# BreakoutV2.net
KiCad netlist of a schematic drawn in EAGLE
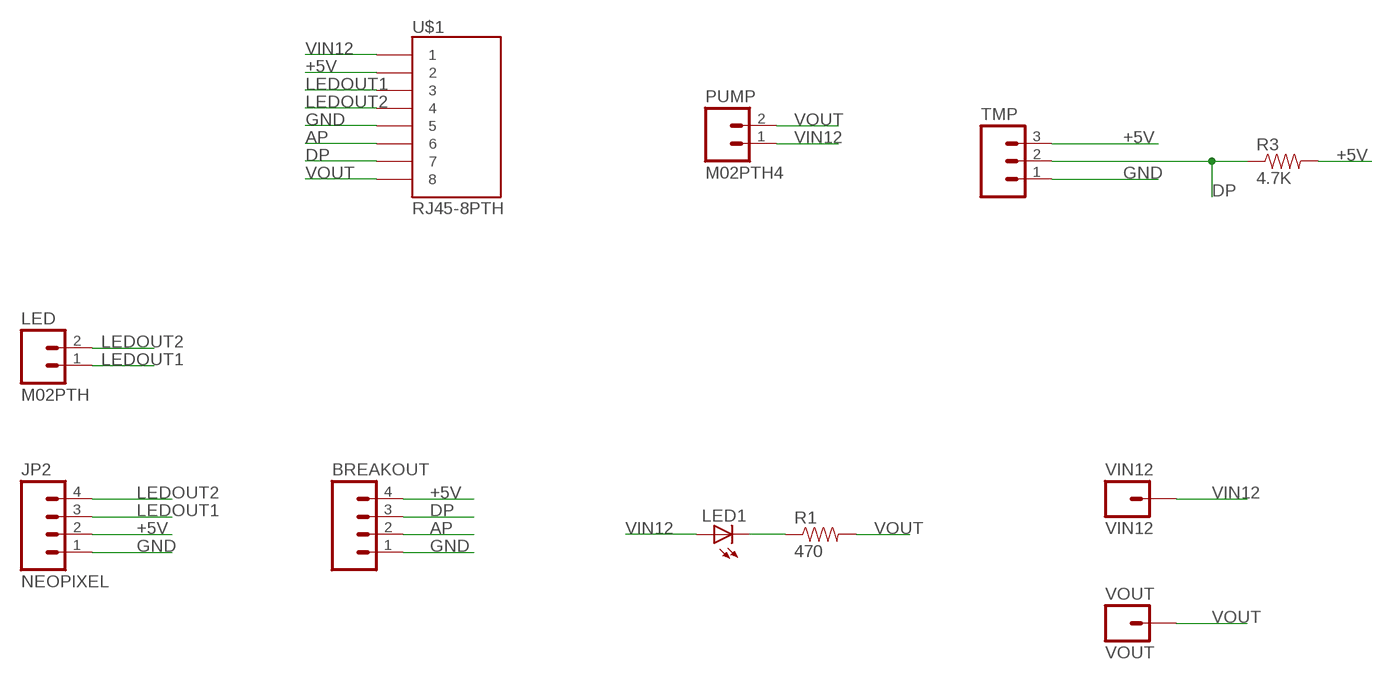
[diagram p0: schematic, sheet 1]

(export (version "E")
  (design (tool "Eeschema 10.0.6"))
  (components
    (comp (ref "BREAKOUT")
      (value "M04PTH")
      (footprint "eagle-import:1X04")
      (libsource (lib "eagle-import") (part "M04PTH"))
    )
    (comp (ref "JP2")
      (value "NEOPIXEL")
      (footprint "eagle-import:1X04")
      (libsource (lib "eagle-import") (part "M04PTH"))
    )
    (comp (ref "LED")
      (value "M02PTH")
      (footprint "eagle-import:1X02")
      (libsource (lib "eagle-import") (part "M02PTH"))
    )
    (comp (ref "LED1")
      (value "LED5MM")
      (footprint "eagle-import:LED5MM")
      (libsource (lib "eagle-import") (part "LED5MM"))
    )
    (comp (ref "PUMP")
      (value "M02PTH4")
      (footprint "eagle-import:1X02_XTRA_BIG")
      (libsource (lib "eagle-import") (part "M02PTH4"))
    )
    (comp (ref "R1")
      (value "470")
      (footprint "eagle-import:1_6W-RES")
      (libsource (lib "eagle-import") (part "RESISTORPTH-1/6W"))
    )
    (comp (ref "R3")
      (value "4.7K")
      (footprint "eagle-import:1_6W-RES")
      (libsource (lib "eagle-import") (part "RESISTORPTH-1/6W"))
    )
    (comp (ref "TMP")
      (value "M03PTH")
      (footprint "eagle-import:1X03")
      (libsource (lib "eagle-import") (part "M03PTH"))
    )
    (comp (ref "U$1")
      (value "RJ45-8PTH")
      (footprint "eagle-import:RJ45-8")
      (libsource (lib "eagle-import") (part "RJ45-8PTH"))
    )
    (comp (ref "VIN12")
      (value "VIN12")
      (footprint "eagle-import:1X01_POGOPIN_HOLE_0.58")
      (libsource (lib "eagle-import") (part "M01POGOPIN_HOLE_0.58"))
    )
    (comp (ref "VOUT")
      (value "VOUT")
      (footprint "eagle-import:1X01_POGOPIN_HOLE_0.58")
      (libsource (lib "eagle-import") (part "M01POGOPIN_HOLE_0.58"))
    )
  )
  (nets
    (net (code "1") (name "/+5V") (class "Default")
      (node (ref "BREAKOUT") (pin "4") (pinfunction "4_4") (pintype "passive"))
      (node (ref "JP2") (pin "2") (pinfunction "2_2") (pintype "passive"))
      (node (ref "R3") (pin "2") (pinfunction "2_2") (pintype "passive"))
      (node (ref "TMP") (pin "3") (pinfunction "3_3") (pintype "passive"))
      (node (ref "U$1") (pin "2") (pinfunction "2_2") (pintype "bidirectional"))
    )
    (net (code "2") (name "/AP") (class "Default")
      (node (ref "BREAKOUT") (pin "2") (pinfunction "2_2") (pintype "passive"))
      (node (ref "U$1") (pin "6") (pinfunction "6_6") (pintype "bidirectional"))
    )
    (net (code "3") (name "/DP") (class "Default")
      (node (ref "BREAKOUT") (pin "3") (pinfunction "3_3") (pintype "passive"))
      (node (ref "R3") (pin "1") (pinfunction "1_1") (pintype "passive"))
      (node (ref "TMP") (pin "2") (pinfunction "2_2") (pintype "passive"))
      (node (ref "U$1") (pin "7") (pinfunction "7_7") (pintype "bidirectional"))
    )
    (net (code "4") (name "/GND") (class "Default")
      (node (ref "BREAKOUT") (pin "1") (pinfunction "1_1") (pintype "passive"))
      (node (ref "JP2") (pin "1") (pinfunction "1_1") (pintype "passive"))
      (node (ref "TMP") (pin "1") (pinfunction "1_1") (pintype "passive"))
      (node (ref "U$1") (pin "5") (pinfunction "5_5") (pintype "bidirectional"))
    )
    (net (code "5") (name "/LEDOUT1") (class "Default")
      (node (ref "JP2") (pin "3") (pinfunction "3_3") (pintype "passive"))
      (node (ref "LED") (pin "1") (pinfunction "1_1") (pintype "passive"))
      (node (ref "U$1") (pin "3") (pinfunction "3_3") (pintype "bidirectional"))
    )
    (net (code "6") (name "/LEDOUT2") (class "Default")
      (node (ref "JP2") (pin "4") (pinfunction "4_4") (pintype "passive"))
      (node (ref "LED") (pin "2") (pinfunction "2_2") (pintype "passive"))
      (node (ref "U$1") (pin "4") (pinfunction "4_4") (pintype "bidirectional"))
    )
    (net (code "7") (name "/VIN12") (class "Default")
      (node (ref "LED1") (pin "A") (pinfunction "A_A") (pintype "passive"))
      (node (ref "PUMP") (pin "1") (pinfunction "1_1") (pintype "passive"))
      (node (ref "U$1") (pin "1") (pinfunction "1_1") (pintype "bidirectional"))
      (node (ref "VIN12") (pin "1") (pinfunction "1_1") (pintype "passive"))
    )
    (net (code "8") (name "/VOUT") (class "Default")
      (node (ref "PUMP") (pin "2") (pinfunction "2_2") (pintype "passive"))
      (node (ref "R1") (pin "2") (pinfunction "2_2") (pintype "passive"))
      (node (ref "U$1") (pin "8") (pinfunction "8_8") (pintype "bidirectional"))
      (node (ref "VOUT") (pin "1") (pinfunction "1_1") (pintype "passive"))
    )
    (net (code "9") (name "Net-(LED1-C)") (class "Default")
      (node (ref "LED1") (pin "K") (pinfunction "C_K") (pintype "passive"))
      (node (ref "R1") (pin "1") (pinfunction "1_1") (pintype "passive"))
    )
  )
)
